# breakout.net
KiCad netlist of a schematic drawn in EAGLE
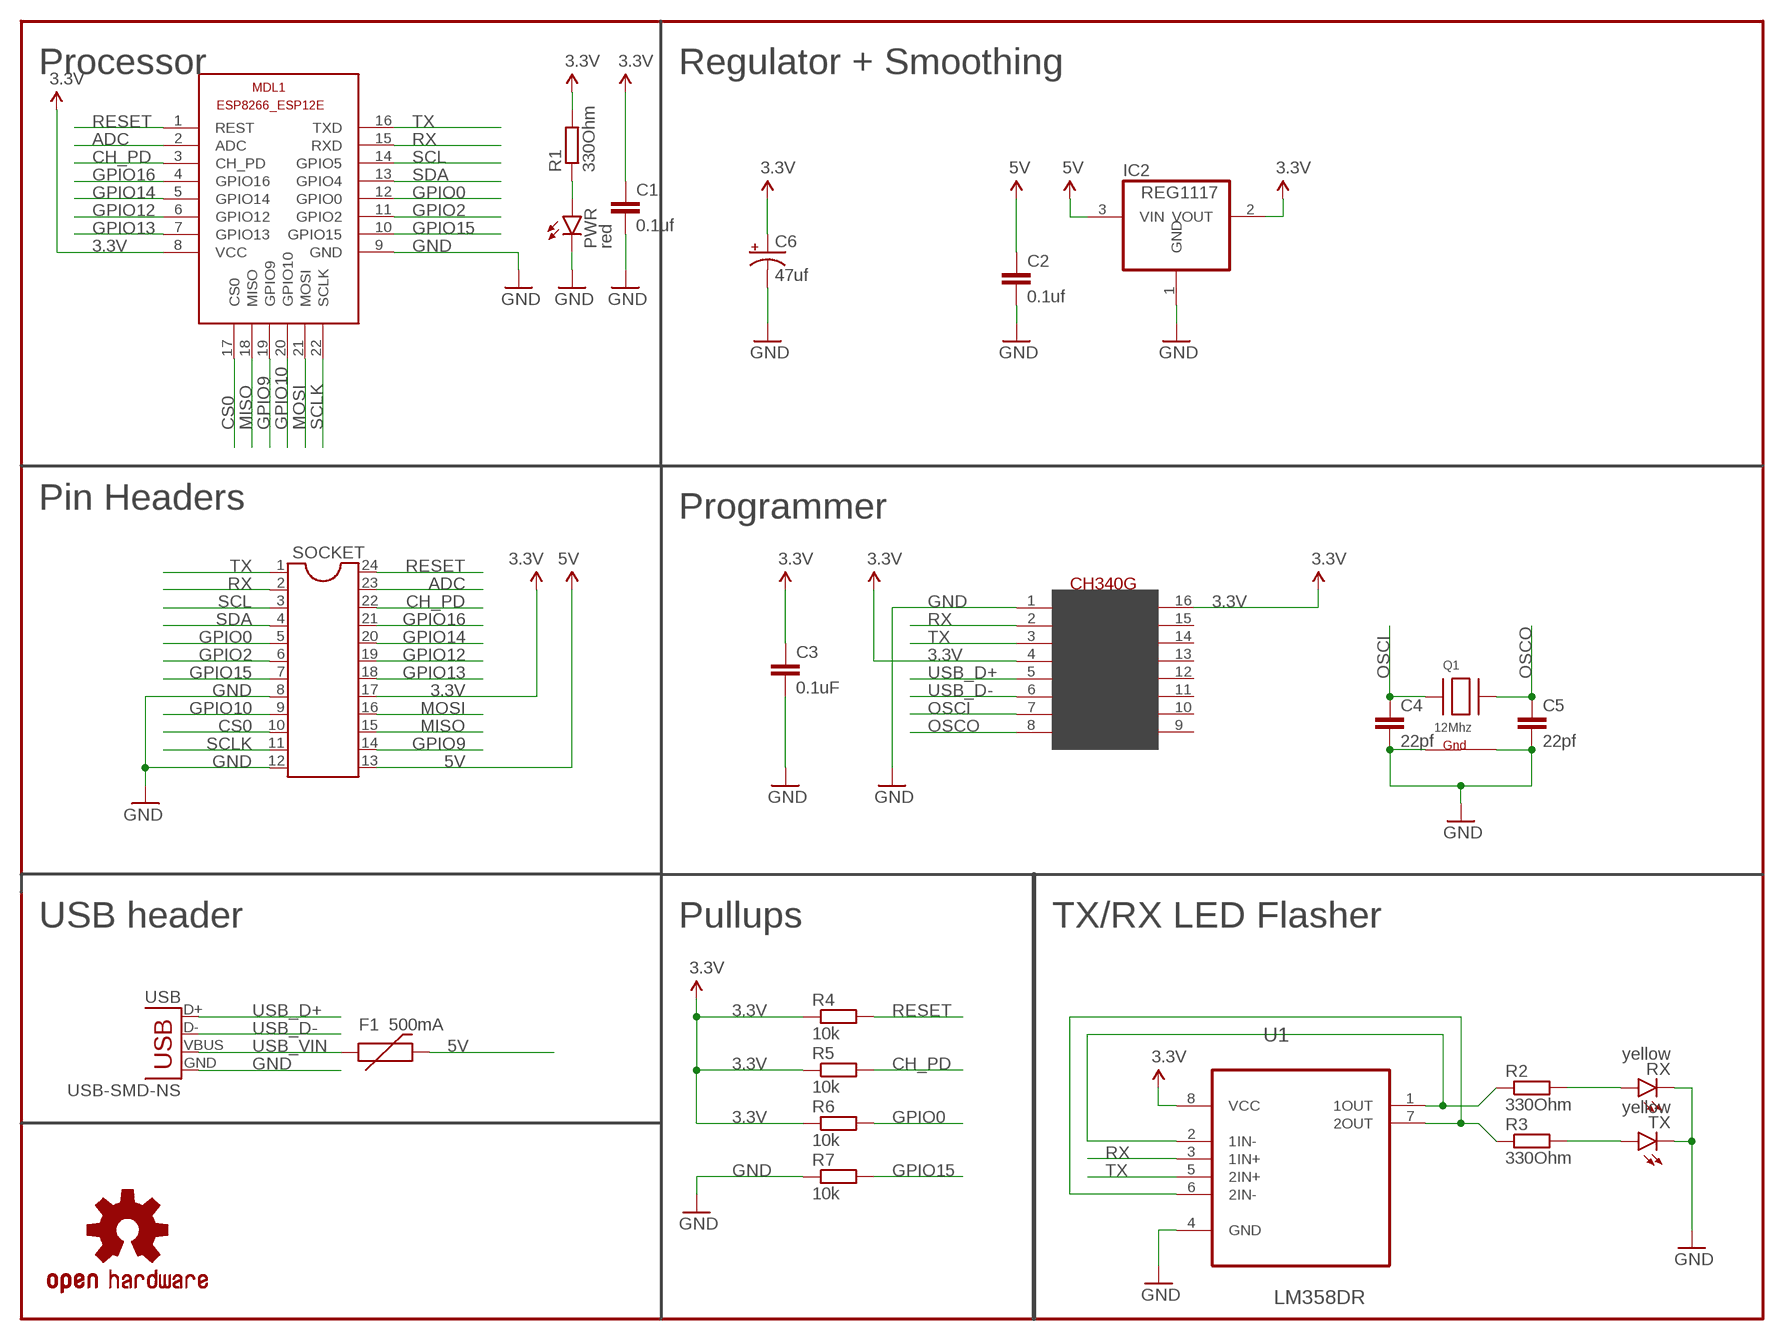
[diagram p0: schematic, sheet 1]

(export (version "E")
  (design (tool "Eeschema 10.0.6"))
  (components
    (comp (ref "C1")
      (value "0.1uf")
      (footprint "eagle-import:C0805")
      (libsource (lib "eagle-import") (part "C-EUC0805"))
    )
    (comp (ref "C2")
      (value "0.1uf")
      (footprint "eagle-import:C0805")
      (libsource (lib "eagle-import") (part "C-EUC0805"))
    )
    (comp (ref "C3")
      (value "0.1uF")
      (footprint "eagle-import:C0805")
      (libsource (lib "eagle-import") (part "C-EUC0805"))
    )
    (comp (ref "C4")
      (value "22pf")
      (footprint "eagle-import:C0805")
      (libsource (lib "eagle-import") (part "C-EUC0805"))
    )
    (comp (ref "C5")
      (value "22pf")
      (footprint "eagle-import:C0805")
      (libsource (lib "eagle-import") (part "C-EUC0805"))
    )
    (comp (ref "C6")
      (value "47uf")
      (footprint "eagle-import:PANASONIC_C")
      (libsource (lib "eagle-import") (part "CAP_POLC"))
    )
    (comp (ref "F1")
      (value "500mA")
      (footprint "eagle-import:PTC-1206")
      (libsource (lib "eagle-import") (part "PTCSMD"))
    )
    (comp (ref "FRAME1")
      (value "FRAME-LETTERNO_PACKAGE")
      (footprint "eagle-import:DUMMY")
      (fields (field (name "DESIGNER") "Nobody"))
      (libsource (lib "eagle-import") (part "FRAME-LETTERNO_PACKAGE"))
    )
    (comp (ref "IC2")
      (value "REG1117")
      (footprint "eagle-import:SOT223")
      (libsource (lib "eagle-import") (part "REG1117"))
    )
    (comp (ref "LOGO1")
      (value "OSHW-LOGOS")
      (footprint "eagle-import:OSHW-LOGO-S")
      (libsource (lib "eagle-import") (part "OSHW-LOGOS"))
    )
    (comp (ref "MDL1")
      (value "ESP8266-12EESP8266-ESP12E")
      (footprint "eagle-import:ESP8266-ESP12E")
      (libsource (lib "eagle-import") (part "ESP8266-12EESP8266-ESP12E"))
    )
    (comp (ref "PWR")
      (value "red")
      (footprint "eagle-import:LED-0603")
      (libsource (lib "eagle-import") (part "LED0603"))
    )
    (comp (ref "Q1")
      (value "12Mhz")
      (footprint "eagle-import:NX3225")
      (libsource (lib "eagle-import") (part "XTAL-4-3225"))
    )
    (comp (ref "R1")
      (value "330Ohm")
      (footprint "eagle-import:R0805")
      (libsource (lib "eagle-import") (part "R-EU_R0805"))
    )
    (comp (ref "R2")
      (value "330Ohm")
      (footprint "eagle-import:R0805")
      (libsource (lib "eagle-import") (part "R-EU_R0805"))
    )
    (comp (ref "R3")
      (value "330Ohm")
      (footprint "eagle-import:R0805")
      (libsource (lib "eagle-import") (part "R-EU_R0805"))
    )
    (comp (ref "R4")
      (value "10k")
      (footprint "eagle-import:R0805")
      (libsource (lib "eagle-import") (part "R-EU_R0805"))
    )
    (comp (ref "R5")
      (value "10k")
      (footprint "eagle-import:R0805")
      (libsource (lib "eagle-import") (part "R-EU_R0805"))
    )
    (comp (ref "R6")
      (value "10k")
      (footprint "eagle-import:R0805")
      (libsource (lib "eagle-import") (part "R-EU_R0805"))
    )
    (comp (ref "R7")
      (value "10k")
      (footprint "eagle-import:R0805")
      (libsource (lib "eagle-import") (part "R-EU_R0805"))
    )
    (comp (ref "RX")
      (value "yellow")
      (footprint "eagle-import:LED-0603")
      (libsource (lib "eagle-import") (part "LED0603"))
    )
    (comp (ref "SOCKET")
      (value "DIL24-9")
      (footprint "eagle-import:DIL24-9")
      (libsource (lib "eagle-import") (part "DIL24-9"))
    )
    (comp (ref "TX")
      (value "yellow")
      (footprint "eagle-import:LED-0603")
      (libsource (lib "eagle-import") (part "LED0603"))
    )
    (comp (ref "U$1")
      (value "CH340G")
      (footprint "eagle-import:SOIC16")
      (libsource (lib "eagle-import") (part "CH340G"))
    )
    (comp (ref "U1")
      (value "LM358DR")
      (footprint "eagle-import:SOIC127P600X175-8N")
      (libsource (lib "eagle-import") (part "LM358DR"))
    )
    (comp (ref "USB")
      (value "USB-SMD-NS")
      (footprint "eagle-import:USB-MINIB-NOSTOP")
      (libsource (lib "eagle-import") (part "USB-SMD-NS"))
    )
  )
  (nets
    (net (code "1") (name "/ADC") (class "Default")
      (node (ref "MDL1") (pin "2") (pinfunction "ADC_2") (pintype "bidirectional"))
      (node (ref "SOCKET") (pin "23") (pinfunction "23_23") (pintype "passive"))
    )
    (net (code "2") (name "/CH_PD") (class "Default")
      (node (ref "MDL1") (pin "3") (pinfunction "CH_PD_3") (pintype "bidirectional"))
      (node (ref "R5") (pin "2") (pinfunction "2_2") (pintype "passive"))
      (node (ref "SOCKET") (pin "22") (pinfunction "22_22") (pintype "passive"))
    )
    (net (code "3") (name "/CS0") (class "Default")
      (node (ref "MDL1") (pin "17") (pinfunction "CS0_17") (pintype "bidirectional"))
      (node (ref "SOCKET") (pin "10") (pinfunction "10_10") (pintype "passive"))
    )
    (net (code "4") (name "/GPIO0") (class "Default")
      (node (ref "MDL1") (pin "12") (pinfunction "GPIO0_12") (pintype "bidirectional"))
      (node (ref "R6") (pin "2") (pinfunction "2_2") (pintype "passive"))
      (node (ref "SOCKET") (pin "5") (pinfunction "5_5") (pintype "passive"))
    )
    (net (code "5") (name "/GPIO2") (class "Default")
      (node (ref "MDL1") (pin "11") (pinfunction "GPIO2_11") (pintype "bidirectional"))
      (node (ref "SOCKET") (pin "6") (pinfunction "6_6") (pintype "passive"))
    )
    (net (code "6") (name "/GPIO9") (class "Default")
      (node (ref "MDL1") (pin "19") (pinfunction "GPIO9_19") (pintype "bidirectional"))
      (node (ref "SOCKET") (pin "14") (pinfunction "14_14") (pintype "passive"))
    )
    (net (code "7") (name "/GPIO10") (class "Default")
      (node (ref "MDL1") (pin "20") (pinfunction "GPIO10_20") (pintype "bidirectional"))
      (node (ref "SOCKET") (pin "9") (pinfunction "9_9") (pintype "passive"))
    )
    (net (code "8") (name "/GPIO12") (class "Default")
      (node (ref "MDL1") (pin "6") (pinfunction "GPIO12_6") (pintype "bidirectional"))
      (node (ref "SOCKET") (pin "19") (pinfunction "19_19") (pintype "passive"))
    )
    (net (code "9") (name "/GPIO13") (class "Default")
      (node (ref "MDL1") (pin "7") (pinfunction "GPIO13_7") (pintype "bidirectional"))
      (node (ref "SOCKET") (pin "18") (pinfunction "18_18") (pintype "passive"))
    )
    (net (code "10") (name "/GPIO14") (class "Default")
      (node (ref "MDL1") (pin "5") (pinfunction "GPIO14_5") (pintype "bidirectional"))
      (node (ref "SOCKET") (pin "20") (pinfunction "20_20") (pintype "passive"))
    )
    (net (code "11") (name "/GPIO15") (class "Default")
      (node (ref "MDL1") (pin "10") (pinfunction "GPIO15_10") (pintype "bidirectional"))
      (node (ref "R7") (pin "2") (pinfunction "2_2") (pintype "passive"))
      (node (ref "SOCKET") (pin "7") (pinfunction "7_7") (pintype "passive"))
    )
    (net (code "12") (name "/GPIO16") (class "Default")
      (node (ref "MDL1") (pin "4") (pinfunction "GPIO16_4") (pintype "bidirectional"))
      (node (ref "SOCKET") (pin "21") (pinfunction "21_21") (pintype "passive"))
    )
    (net (code "13") (name "/MISO") (class "Default")
      (node (ref "MDL1") (pin "18") (pinfunction "MISO_18") (pintype "bidirectional"))
      (node (ref "SOCKET") (pin "15") (pinfunction "15_15") (pintype "passive"))
    )
    (net (code "14") (name "/MOSI") (class "Default")
      (node (ref "MDL1") (pin "21") (pinfunction "MOSI_21") (pintype "bidirectional"))
      (node (ref "SOCKET") (pin "16") (pinfunction "16_16") (pintype "passive"))
    )
    (net (code "15") (name "/OSCI") (class "Default")
      (node (ref "C4") (pin "1") (pinfunction "1_1") (pintype "passive"))
      (node (ref "Q1") (pin "1") (pinfunction "X1_1") (pintype "bidirectional"))
      (node (ref "U$1") (pin "7") (pinfunction "XI_7") (pintype "bidirectional"))
    )
    (net (code "16") (name "/OSCO") (class "Default")
      (node (ref "C5") (pin "1") (pinfunction "1_1") (pintype "passive"))
      (node (ref "Q1") (pin "3") (pinfunction "X2_3") (pintype "bidirectional"))
      (node (ref "U$1") (pin "8") (pinfunction "XO_8") (pintype "bidirectional"))
    )
    (net (code "17") (name "/RESET") (class "Default")
      (node (ref "MDL1") (pin "1") (pinfunction "REST_1") (pintype "bidirectional"))
      (node (ref "R4") (pin "2") (pinfunction "2_2") (pintype "passive"))
      (node (ref "SOCKET") (pin "24") (pinfunction "24_24") (pintype "passive"))
    )
    (net (code "18") (name "/RX") (class "Default")
      (node (ref "MDL1") (pin "15") (pinfunction "RXD_15") (pintype "bidirectional"))
      (node (ref "SOCKET") (pin "2") (pinfunction "2_2") (pintype "passive"))
      (node (ref "U$1") (pin "2") (pinfunction "TX_2") (pintype "bidirectional"))
      (node (ref "U1") (pin "3") (pinfunction "1IN+_3") (pintype "input"))
    )
    (net (code "19") (name "/SCL") (class "Default")
      (node (ref "MDL1") (pin "14") (pinfunction "GPIO5_14") (pintype "bidirectional"))
      (node (ref "SOCKET") (pin "3") (pinfunction "3_3") (pintype "passive"))
    )
    (net (code "20") (name "/SCLK") (class "Default")
      (node (ref "MDL1") (pin "22") (pinfunction "SCLK_22") (pintype "bidirectional"))
      (node (ref "SOCKET") (pin "11") (pinfunction "11_11") (pintype "passive"))
    )
    (net (code "21") (name "/SDA") (class "Default")
      (node (ref "MDL1") (pin "13") (pinfunction "GPIO4_13") (pintype "bidirectional"))
      (node (ref "SOCKET") (pin "4") (pinfunction "4_4") (pintype "passive"))
    )
    (net (code "22") (name "/TX") (class "Default")
      (node (ref "MDL1") (pin "16") (pinfunction "TXD_16") (pintype "bidirectional"))
      (node (ref "SOCKET") (pin "1") (pinfunction "1_1") (pintype "passive"))
      (node (ref "U$1") (pin "3") (pinfunction "RX_3") (pintype "bidirectional"))
      (node (ref "U1") (pin "5") (pinfunction "2IN+_5") (pintype "input"))
    )
    (net (code "23") (name "/USB_D+") (class "Default")
      (node (ref "U$1") (pin "5") (pinfunction "D+_5") (pintype "bidirectional"))
      (node (ref "USB") (pin "D+") (pinfunction "D+_D+") (pintype "bidirectional"))
    )
    (net (code "24") (name "/USB_D-") (class "Default")
      (node (ref "U$1") (pin "6") (pinfunction "D-_6") (pintype "bidirectional"))
      (node (ref "USB") (pin "D-") (pinfunction "D-_D-") (pintype "bidirectional"))
    )
    (net (code "25") (name "/USB_VIN") (class "Default")
      (node (ref "F1") (pin "1") (pinfunction "1_1") (pintype "bidirectional"))
      (node (ref "USB") (pin "VBUS") (pinfunction "VBUS_VBUS") (pintype "bidirectional"))
    )
    (net (code "26") (name "3.3V") (class "Default")
      (node (ref "C1") (pin "1") (pinfunction "1_1") (pintype "passive"))
      (node (ref "C3") (pin "1") (pinfunction "1_1") (pintype "passive"))
      (node (ref "C6") (pin "+") (pinfunction "+_+") (pintype "passive"))
      (node (ref "IC2") (pin "2") (pinfunction "VOUT_2") (pintype "output"))
      (node (ref "MDL1") (pin "8") (pinfunction "VCC_8") (pintype "bidirectional"))
      (node (ref "R1") (pin "2") (pinfunction "2_2") (pintype "passive"))
      (node (ref "R4") (pin "1") (pinfunction "1_1") (pintype "passive"))
      (node (ref "R5") (pin "1") (pinfunction "1_1") (pintype "passive"))
      (node (ref "R6") (pin "1") (pinfunction "1_1") (pintype "passive"))
      (node (ref "SOCKET") (pin "17") (pinfunction "17_17") (pintype "passive"))
      (node (ref "U$1") (pin "16") (pinfunction "VCC_16") (pintype "bidirectional"))
      (node (ref "U$1") (pin "4") (pinfunction "V3_4") (pintype "bidirectional"))
      (node (ref "U1") (pin "8") (pinfunction "VCC_8") (pintype "power_in"))
    )
    (net (code "27") (name "5V") (class "Default")
      (node (ref "C2") (pin "1") (pinfunction "1_1") (pintype "passive"))
      (node (ref "F1") (pin "2") (pinfunction "2_2") (pintype "bidirectional"))
      (node (ref "IC2") (pin "3") (pinfunction "VIN_3") (pintype "input"))
      (node (ref "SOCKET") (pin "13") (pinfunction "13_13") (pintype "passive"))
    )
    (net (code "28") (name "GND") (class "Default")
      (node (ref "C1") (pin "2") (pinfunction "2_2") (pintype "passive"))
      (node (ref "C2") (pin "2") (pinfunction "2_2") (pintype "passive"))
      (node (ref "C3") (pin "2") (pinfunction "2_2") (pintype "passive"))
      (node (ref "C4") (pin "2") (pinfunction "2_2") (pintype "passive"))
      (node (ref "C5") (pin "2") (pinfunction "2_2") (pintype "passive"))
      (node (ref "C6") (pin "-") (pinfunction "-_-") (pintype "passive"))
      (node (ref "IC2") (pin "1") (pinfunction "GND_1") (pintype "power_in"))
      (node (ref "MDL1") (pin "9") (pinfunction "GND_9") (pintype "bidirectional"))
      (node (ref "PWR") (pin "C") (pinfunction "C_C") (pintype "passive"))
      (node (ref "Q1") (pin "2") (pinfunction "G2_2") (pintype "power_in"))
      (node (ref "Q1") (pin "4") (pinfunction "G1_4") (pintype "power_in"))
      (node (ref "R7") (pin "1") (pinfunction "1_1") (pintype "passive"))
      (node (ref "RX") (pin "C") (pinfunction "C_C") (pintype "passive"))
      (node (ref "SOCKET") (pin "12") (pinfunction "12_12") (pintype "passive"))
      (node (ref "SOCKET") (pin "8") (pinfunction "8_8") (pintype "passive"))
      (node (ref "TX") (pin "C") (pinfunction "C_C") (pintype "passive"))
      (node (ref "U$1") (pin "1") (pinfunction "GND_1") (pintype "bidirectional"))
      (node (ref "U1") (pin "4") (pinfunction "GND_4") (pintype "passive"))
      (node (ref "USB") (pin "GND") (pinfunction "GND_GND") (pintype "bidirectional"))
    )
    (net (code "29") (name "Net-(PWR-PadA)") (class "Default")
      (node (ref "PWR") (pin "A") (pinfunction "A_A") (pintype "passive"))
      (node (ref "R1") (pin "1") (pinfunction "1_1") (pintype "passive"))
    )
    (net (code "30") (name "Net-(R2-Pad2)") (class "Default")
      (node (ref "R2") (pin "2") (pinfunction "2_2") (pintype "passive"))
      (node (ref "RX") (pin "A") (pinfunction "A_A") (pintype "passive"))
    )
    (net (code "31") (name "Net-(R3-Pad2)") (class "Default")
      (node (ref "R3") (pin "2") (pinfunction "2_2") (pintype "passive"))
      (node (ref "TX") (pin "A") (pinfunction "A_A") (pintype "passive"))
    )
    (net (code "32") (name "Net-(U1-1IN-)") (class "Default")
      (node (ref "R2") (pin "1") (pinfunction "1_1") (pintype "passive"))
      (node (ref "U1") (pin "1") (pinfunction "1OUT_1") (pintype "output"))
      (node (ref "U1") (pin "2") (pinfunction "1IN-_2") (pintype "input"))
    )
    (net (code "33") (name "Net-(U1-2IN-)") (class "Default")
      (node (ref "R3") (pin "1") (pinfunction "1_1") (pintype "passive"))
      (node (ref "U1") (pin "6") (pinfunction "2IN-_6") (pintype "input"))
      (node (ref "U1") (pin "7") (pinfunction "2OUT_7") (pintype "output"))
    )
    (net (code "34") (name "unconnected-(U$1-CTS-Pad9)") (class "Default")
      (node (ref "U$1") (pin "9") (pinfunction "CTS_9") (pintype "bidirectional"))
    )
    (net (code "35") (name "unconnected-(U$1-DCD-Pad12)") (class "Default")
      (node (ref "U$1") (pin "12") (pinfunction "DCD_12") (pintype "bidirectional"))
    )
    (net (code "36") (name "unconnected-(U$1-DSR-Pad10)") (class "Default")
      (node (ref "U$1") (pin "10") (pinfunction "DSR_10") (pintype "bidirectional"))
    )
    (net (code "37") (name "unconnected-(U$1-DTR-Pad13)") (class "Default")
      (node (ref "U$1") (pin "13") (pinfunction "DTR_13") (pintype "bidirectional"))
    )
    (net (code "38") (name "unconnected-(U$1-RI-Pad11)") (class "Default")
      (node (ref "U$1") (pin "11") (pinfunction "RI_11") (pintype "bidirectional"))
    )
    (net (code "39") (name "unconnected-(U$1-RS232-Pad15)") (class "Default")
      (node (ref "U$1") (pin "15") (pinfunction "RS232_15") (pintype "bidirectional"))
    )
    (net (code "40") (name "unconnected-(U$1-RTS-Pad14)") (class "Default")
      (node (ref "U$1") (pin "14") (pinfunction "RTS_14") (pintype "bidirectional"))
    )
  )
)
